# ICs.net
KiCad netlist of a schematic drawn in Altium Designer
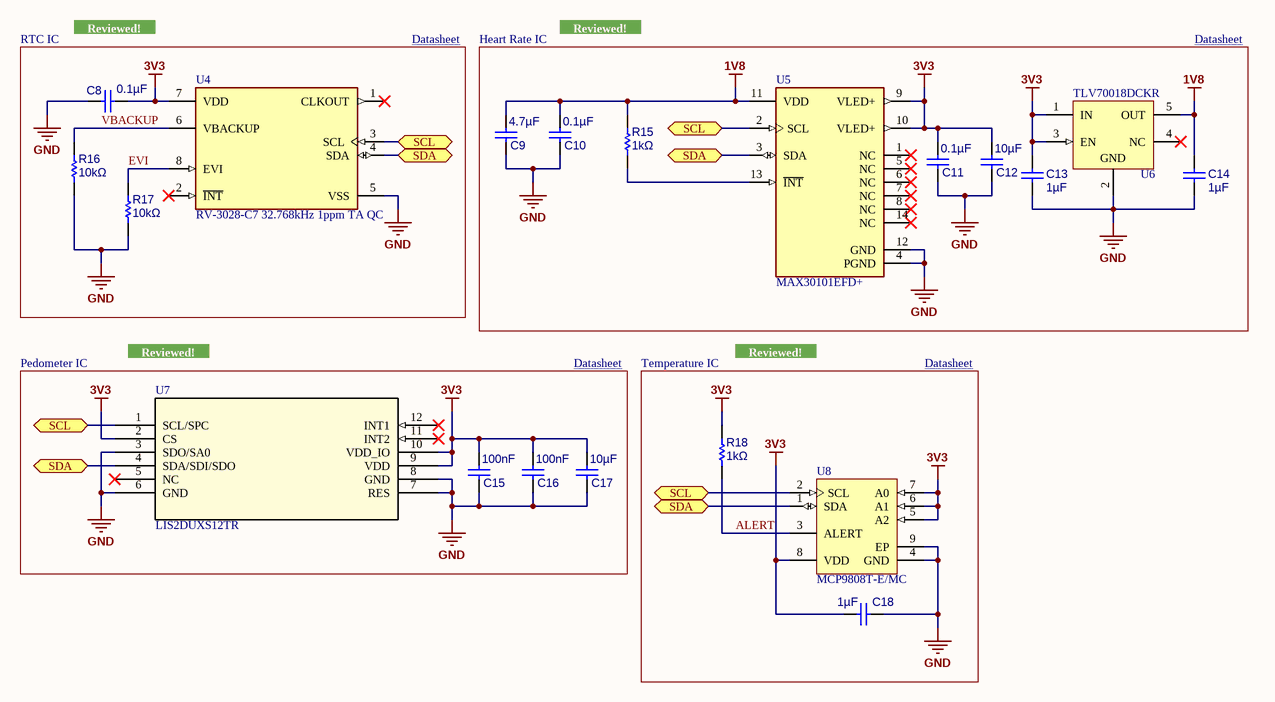
[diagram p0: ICs.SchDoc]

(export (version "E")
  (design (tool "Eeschema 10.0.6"))
  (components
    (comp (ref "C8")
      (value "0.1µF")
      (footprint "WCAP-CSGP_0603_L1.6W0.8H0.8_Reflow")
      (description "10V tolerance")
      (libsource (lib "Altium Content Vault") (part "Capacitor_Non-Polarized"))
    )
    (comp (ref "C9")
      (value "4.7µF")
      (footprint "WCAP-CSGP_0603_L1.6W0.8H0.8_Reflow")
      (description "10V tolerance")
      (libsource (lib "Altium Content Vault") (part "Capacitor_Non-Polarized"))
    )
    (comp (ref "C10")
      (value "0.1µF")
      (footprint "WCAP-CSGP_0603_L1.6W0.8H0.8_Reflow")
      (description "10V tolerance")
      (libsource (lib "Altium Content Vault") (part "Capacitor_Non-Polarized"))
    )
    (comp (ref "C11")
      (value "0.1µF")
      (footprint "WCAP-CSGP_0603_L1.6W0.8H0.8_Reflow")
      (description "10V tolerance")
      (libsource (lib "Altium Content Vault") (part "Capacitor_Non-Polarized"))
    )
    (comp (ref "C12")
      (value "10µF")
      (footprint "WCAP-CSGP_0603_L1.6W0.8H0.8_Reflow")
      (description "10V tolerance")
      (libsource (lib "Altium Content Vault") (part "Capacitor_Non-Polarized"))
    )
    (comp (ref "C13")
      (value "1µF")
      (footprint "WCAP-CSGP_0603_L1.6W0.8H0.8_Reflow")
      (description "10V tolerance")
      (libsource (lib "Altium Content Vault") (part "Capacitor_Non-Polarized"))
    )
    (comp (ref "C14")
      (value "1µF")
      (footprint "WCAP-CSGP_0603_L1.6W0.8H0.8_Reflow")
      (description "10V tolerance")
      (libsource (lib "Altium Content Vault") (part "Capacitor_Non-Polarized"))
    )
    (comp (ref "C15")
      (value "100nF")
      (footprint "WCAP-CSGP_0603_L1.6W0.8H0.8_Reflow")
      (description "10V tolerance")
      (libsource (lib "Altium Content Vault") (part "Capacitor_Non-Polarized"))
    )
    (comp (ref "C16")
      (value "100nF")
      (footprint "WCAP-CSGP_0603_L1.6W0.8H0.8_Reflow")
      (description "10V tolerance")
      (libsource (lib "Altium Content Vault") (part "Capacitor_Non-Polarized"))
    )
    (comp (ref "C17")
      (value "10µF")
      (footprint "WCAP-CSGP_0603_L1.6W0.8H0.8_Reflow")
      (description "10V tolerance")
      (libsource (lib "Altium Content Vault") (part "Capacitor_Non-Polarized"))
    )
    (comp (ref "C18")
      (value "1µF")
      (footprint "WCAP-CSGP_0603_L1.6W0.8H0.8_Reflow")
      (description "10V tolerance")
      (libsource (lib "Altium Content Vault") (part "Capacitor_Non-Polarized"))
    )
    (comp (ref "R15")
      (value "1kΩ")
      (footprint "RESC1608X55X25NL10T15")
      (libsource (lib "Altium Content Vault") (part "RES"))
    )
    (comp (ref "R16")
      (value "10kΩ")
      (footprint "RESC1608X55X25NL10T15")
      (libsource (lib "Altium Content Vault") (part "RES"))
    )
    (comp (ref "R17")
      (value "10kΩ")
      (footprint "RESC1608X55X25NL10T15")
      (libsource (lib "Altium Content Vault") (part "RES"))
    )
    (comp (ref "R18")
      (value "1kΩ")
      (footprint "RESC1608X55X25NL10T15")
      (libsource (lib "Altium Content Vault") (part "RES"))
    )
    (comp (ref "U4")
      (value "RV-3028-C7 32.768kHz 1ppm TA QC")
      (footprint "FP-RV-3028-C7_32_768kHz_1-MFG")
      (description "Real Time Clock Serial 2byte Clock/Calendar/Alarm/Timer/Battery Backup 8-Pin CSMD T/R")
      (fields
        (field (name "OCTOPART") "https://octopart.com/rv-3028-c7+32.768khz+1ppm+ta+qc-micro+crystal-98880451")
        (field (name "MANUFACTURER") "Micro Crystal")
      )
      (libsource (lib "Altium Content Vault") (part "f06799675b941e5ee1fb77ef065374c"))
    )
    (comp (ref "U5")
      (value "MAX30101EFD+")
      (footprint "FP-F143A5-1-MFG")
      (description "INTEGRATED OPTICAL SENSOR")
      (fields
        (field (name "MANUFACTURER") "Maxim Integrated")
        (field (name "OCTOPART") "https://octopart.com/max30101efd%2B-maxim+integrated-57054333")
      )
      (libsource (lib "Altium Content Vault") (part "7412f82398c18c21c59cad441ae59a4"))
    )
    (comp (ref "U6")
      (value "TLV70018DCKR")
      (footprint "DCK0005A_L")
      (fields (field (name "MANUFACTURER") "Texas Instruments"))
      (libsource (lib "Altium Content Vault") (part "TI-TXX7XXXX-5"))
    )
    (comp (ref "U7")
      (value "LIS2DUXS12TR")
      (footprint "QFN_DUXS12_STM")
      (fields (field (name "COPYRIGHT") "Copyright (C) 2025 Ultra Librarian. All rights reserved."))
      (libsource (lib "LIS2DUXS12TR") (part "LIS2DUXS12TR"))
    )
    (comp (ref "U8")
      (value "MCP9808T-E/MC")
      (footprint "MCHP-DFN-MC8_V")
      (fields (field (name "MANUFACTURER") "Microchip"))
      (libsource (lib "Altium Content Vault") (part "MCHP-MCP9808-DFN-8"))
    )
  )
  (nets
    (net (code "1") (name "/ALERT") (class "Default")
      (node (ref "R18") (pin "1") (pinfunction "1_1") (pintype "passive"))
      (node (ref "U8") (pin "3") (pinfunction "ALERT_3") (pintype "open_collector"))
    )
    (net (code "2") (name "/EVI") (class "Default")
      (node (ref "R17") (pin "2") (pinfunction "2_2") (pintype "passive"))
      (node (ref "U4") (pin "8") (pinfunction "EVI_8") (pintype "input"))
    )
    (net (code "3") (name "/SCL") (class "Default")
      (node (ref "U4") (pin "3") (pinfunction "SCL_3") (pintype "input"))
      (node (ref "U5") (pin "2") (pinfunction "SCL_2") (pintype "input"))
      (node (ref "U7") (pin "1") (pinfunction "SCL/SPC_1") (pintype "passive"))
      (node (ref "U8") (pin "2") (pinfunction "SCL_2") (pintype "input"))
    )
    (net (code "4") (name "/SDA") (class "Default")
      (node (ref "U4") (pin "4") (pinfunction "SDA_4") (pintype "bidirectional"))
      (node (ref "U5") (pin "3") (pinfunction "SDA_3") (pintype "bidirectional"))
      (node (ref "U7") (pin "4") (pinfunction "SDA/SDI/SDO_4") (pintype "passive"))
      (node (ref "U8") (pin "1") (pinfunction "SDA_1") (pintype "bidirectional"))
    )
    (net (code "5") (name "/VBACKUP") (class "Default")
      (node (ref "R16") (pin "2") (pinfunction "2_2") (pintype "passive"))
      (node (ref "U4") (pin "6") (pinfunction "VBACKUP_6") (pintype "power_in"))
    )
    (net (code "6") (name "1V8") (class "Default")
      (node (ref "C10") (pin "1") (pinfunction "1_1") (pintype "passive"))
      (node (ref "C14") (pin "2") (pinfunction "2_2") (pintype "passive"))
      (node (ref "C9") (pin "1") (pinfunction "1_1") (pintype "passive"))
      (node (ref "R15") (pin "2") (pinfunction "2_2") (pintype "passive"))
      (node (ref "U5") (pin "11") (pinfunction "VDD_11") (pintype "power_in"))
      (node (ref "U6") (pin "5") (pinfunction "OUT_5") (pintype "power_in"))
    )
    (net (code "7") (name "3V3") (class "Default")
      (node (ref "C11") (pin "1") (pinfunction "1_1") (pintype "passive"))
      (node (ref "C12") (pin "1") (pinfunction "1_1") (pintype "passive"))
      (node (ref "C13") (pin "2") (pinfunction "2_2") (pintype "passive"))
      (node (ref "C15") (pin "1") (pinfunction "1_1") (pintype "passive"))
      (node (ref "C16") (pin "1") (pinfunction "1_1") (pintype "passive"))
      (node (ref "C17") (pin "1") (pinfunction "1_1") (pintype "passive"))
      (node (ref "C18") (pin "1") (pinfunction "1_1") (pintype "passive"))
      (node (ref "C8") (pin "1") (pinfunction "1_1") (pintype "passive"))
      (node (ref "R18") (pin "2") (pinfunction "2_2") (pintype "passive"))
      (node (ref "U4") (pin "7") (pinfunction "VDD_7") (pintype "power_in"))
      (node (ref "U5") (pin "10") (pinfunction "VLED+_10") (pintype "output"))
      (node (ref "U5") (pin "9") (pinfunction "VLED+_9") (pintype "output"))
      (node (ref "U6") (pin "1") (pinfunction "IN_1") (pintype "power_in"))
      (node (ref "U6") (pin "3") (pinfunction "EN_3") (pintype "input"))
      (node (ref "U7") (pin "10") (pinfunction "VDD_IO_10") (pintype "power_in"))
      (node (ref "U7") (pin "2") (pinfunction "CS_2") (pintype "passive"))
      (node (ref "U7") (pin "9") (pinfunction "VDD_9") (pintype "power_in"))
      (node (ref "U8") (pin "5") (pinfunction "A2_5") (pintype "input"))
      (node (ref "U8") (pin "6") (pinfunction "A1_6") (pintype "input"))
      (node (ref "U8") (pin "7") (pinfunction "A0_7") (pintype "input"))
      (node (ref "U8") (pin "8") (pinfunction "VDD_8") (pintype "power_in"))
    )
    (net (code "8") (name "GND") (class "Default")
      (node (ref "C10") (pin "2") (pinfunction "2_2") (pintype "passive"))
      (node (ref "C11") (pin "2") (pinfunction "2_2") (pintype "passive"))
      (node (ref "C12") (pin "2") (pinfunction "2_2") (pintype "passive"))
      (node (ref "C13") (pin "1") (pinfunction "1_1") (pintype "passive"))
      (node (ref "C14") (pin "1") (pinfunction "1_1") (pintype "passive"))
      (node (ref "C15") (pin "2") (pinfunction "2_2") (pintype "passive"))
      (node (ref "C16") (pin "2") (pinfunction "2_2") (pintype "passive"))
      (node (ref "C17") (pin "2") (pinfunction "2_2") (pintype "passive"))
      (node (ref "C18") (pin "2") (pinfunction "2_2") (pintype "passive"))
      (node (ref "C8") (pin "2") (pinfunction "2_2") (pintype "passive"))
      (node (ref "C9") (pin "2") (pinfunction "2_2") (pintype "passive"))
      (node (ref "R16") (pin "1") (pinfunction "1_1") (pintype "passive"))
      (node (ref "R17") (pin "1") (pinfunction "1_1") (pintype "passive"))
      (node (ref "U4") (pin "5") (pinfunction "VSS_5") (pintype "power_in"))
      (node (ref "U5") (pin "12") (pinfunction "GND_12") (pintype "power_in"))
      (node (ref "U5") (pin "4") (pinfunction "PGND_4") (pintype "power_in"))
      (node (ref "U6") (pin "2") (pinfunction "GND_2") (pintype "power_in"))
      (node (ref "U7") (pin "3") (pinfunction "SDO/SA0_3") (pintype "passive"))
      (node (ref "U7") (pin "6") (pinfunction "GND_6") (pintype "power_in"))
      (node (ref "U7") (pin "7") (pinfunction "RES_7") (pintype "passive"))
      (node (ref "U7") (pin "8") (pinfunction "GND_8") (pintype "power_in"))
      (node (ref "U8") (pin "4") (pinfunction "GND_4") (pintype "power_in"))
      (node (ref "U8") (pin "9") (pinfunction "EP_9") (pintype "power_in"))
    )
    (net (code "9") (name "Net-(U5-~{INT})") (class "Default")
      (node (ref "R15") (pin "1") (pinfunction "1_1") (pintype "passive"))
      (node (ref "U5") (pin "13") (pinfunction "~{INT}_13") (pintype "input"))
    )
    (net (code "10") (name "unconnected-(U4-CLKOUT-Pad1)") (class "Default")
      (node (ref "U4") (pin "1") (pinfunction "CLKOUT_1") (pintype "output+no_connect"))
    )
    (net (code "11") (name "unconnected-(U4-~{INT}-Pad2)") (class "Default")
      (node (ref "U4") (pin "2") (pinfunction "~{INT}_2") (pintype "input+no_connect"))
    )
    (net (code "12") (name "unconnected-(U5-NC-Pad1)") (class "Default")
      (node (ref "U5") (pin "1") (pinfunction "NC_1") (pintype "passive+no_connect"))
    )
    (net (code "13") (name "unconnected-(U5-NC-Pad5)") (class "Default")
      (node (ref "U5") (pin "5") (pinfunction "NC_5") (pintype "passive+no_connect"))
    )
    (net (code "14") (name "unconnected-(U5-NC-Pad6)") (class "Default")
      (node (ref "U5") (pin "6") (pinfunction "NC_6") (pintype "passive+no_connect"))
    )
    (net (code "15") (name "unconnected-(U5-NC-Pad7)") (class "Default")
      (node (ref "U5") (pin "7") (pinfunction "NC_7") (pintype "passive+no_connect"))
    )
    (net (code "16") (name "unconnected-(U5-NC-Pad8)") (class "Default")
      (node (ref "U5") (pin "8") (pinfunction "NC_8") (pintype "passive+no_connect"))
    )
    (net (code "17") (name "unconnected-(U5-NC-Pad14)") (class "Default")
      (node (ref "U5") (pin "14") (pinfunction "NC_14") (pintype "passive+no_connect"))
    )
    (net (code "18") (name "unconnected-(U6-NC-Pad4)") (class "Default")
      (node (ref "U6") (pin "4") (pinfunction "NC_4") (pintype "passive+no_connect"))
    )
    (net (code "19") (name "unconnected-(U7-INT1-Pad12)") (class "Default")
      (node (ref "U7") (pin "12") (pinfunction "INT1_12") (pintype "input+no_connect"))
    )
    (net (code "20") (name "unconnected-(U7-INT2-Pad11)") (class "Default")
      (node (ref "U7") (pin "11") (pinfunction "INT2_11") (pintype "input+no_connect"))
    )
    (net (code "21") (name "unconnected-(U7-NC-Pad5)") (class "Default")
      (node (ref "U7") (pin "5") (pinfunction "NC_5") (pintype "passive+no_connect"))
    )
  )
)
